# non_inverting_amplifier_2.net
KiCad netlist of a schematic drawn in EAGLE
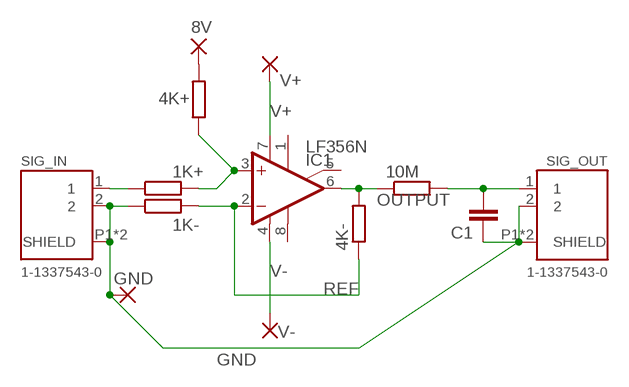
[diagram p0: schematic, sheet 1]

(export (version "E")
  (design (tool "Eeschema 10.0.6"))
  (components
    (comp (ref "1K+")
      (value "R-EU_0207/12")
      (footprint "eagle-import:0207_12")
      (libsource (lib "eagle-import") (part "R-EU_0207/12"))
    )
    (comp (ref "1K-")
      (value "R-EU_0207/12")
      (footprint "eagle-import:0207_12")
      (libsource (lib "eagle-import") (part "R-EU_0207/12"))
    )
    (comp (ref "4K+")
      (value "R-EU_0207/12")
      (footprint "eagle-import:0207_12")
      (libsource (lib "eagle-import") (part "R-EU_0207/12"))
    )
    (comp (ref "4K-")
      (value "R-EU_0207/12")
      (footprint "eagle-import:0207_12")
      (libsource (lib "eagle-import") (part "R-EU_0207/12"))
    )
    (comp (ref "8V")
      (value "2,54/1,1")
      (footprint "eagle-import:2,54_1,1")
      (libsource (lib "eagle-import") (part "2,54/1,1"))
    )
    (comp (ref "10M")
      (value "R-EU_0207/12")
      (footprint "eagle-import:0207_12")
      (libsource (lib "eagle-import") (part "R-EU_0207/12"))
    )
    (comp (ref "C1")
      (value "C2,5-3")
      (footprint "eagle-import:C2.5-3")
      (libsource (lib "eagle-import") (part "C2,5-3"))
    )
    (comp (ref "GND")
      (value "2,54/1,1")
      (footprint "eagle-import:2,54_1,1")
      (libsource (lib "eagle-import") (part "2,54/1,1"))
    )
    (comp (ref "IC1")
      (value "LF356N")
      (footprint "eagle-import:DIL08")
      (libsource (lib "eagle-import") (part "LF356N"))
    )
    (comp (ref "SIG_IN")
      (value "1-1337543-0")
      (footprint "eagle-import:CONN_1-1337543-0")
      (fields (field (name "DIGI-KEY_PART_NUMBER") "A97553-ND") (field (name "MF") "TE Connectivity"))
      (libsource (lib "eagle-import") (part "1-1337543-0"))
    )
    (comp (ref "SIG_OUT")
      (value "1-1337543-0")
      (footprint "eagle-import:CONN_1-1337543-0")
      (fields (field (name "DIGI-KEY_PART_NUMBER") "A97553-ND") (field (name "MF") "TE Connectivity"))
      (libsource (lib "eagle-import") (part "1-1337543-0"))
    )
    (comp (ref "V+")
      (value "2,54/1,1")
      (footprint "eagle-import:2,54_1,1")
      (libsource (lib "eagle-import") (part "2,54/1,1"))
    )
    (comp (ref "V-")
      (value "2,54/1,1")
      (footprint "eagle-import:2,54_1,1")
      (libsource (lib "eagle-import") (part "2,54/1,1"))
    )
  )
  (nets
    (net (code "1") (name "/GND") (class "Default")
      (node (ref "1K-") (pin "1") (pinfunction "1_1") (pintype "passive"))
      (node (ref "C1") (pin "1") (pinfunction "1_1") (pintype "passive"))
      (node (ref "GND") (pin "1") (pinfunction "P_1") (pintype "passive"))
      (node (ref "SIG_IN") (pin "2") (pinfunction "2_2") (pintype "passive"))
      (node (ref "SIG_IN") (pin "P1") (pinfunction "SHIELD_P1") (pintype "passive"))
      (node (ref "SIG_IN") (pin "P2") (pinfunction "SHIELD_P2") (pintype "passive"))
      (node (ref "SIG_OUT") (pin "2") (pinfunction "2_2") (pintype "passive"))
      (node (ref "SIG_OUT") (pin "P1") (pinfunction "SHIELD_P1") (pintype "passive"))
      (node (ref "SIG_OUT") (pin "P2") (pinfunction "SHIELD_P2") (pintype "passive"))
    )
    (net (code "2") (name "/OUTPUT") (class "Default")
      (node (ref "10M") (pin "1") (pinfunction "1_1") (pintype "passive"))
      (node (ref "4K-") (pin "2") (pinfunction "2_2") (pintype "passive"))
      (node (ref "IC1") (pin "6") (pinfunction "OUT_6") (pintype "output"))
    )
    (net (code "3") (name "/REF") (class "Default")
      (node (ref "1K-") (pin "2") (pinfunction "2_2") (pintype "passive"))
      (node (ref "4K-") (pin "1") (pinfunction "1_1") (pintype "passive"))
      (node (ref "IC1") (pin "2") (pinfunction "-IN_2") (pintype "input"))
    )
    (net (code "4") (name "/V+") (class "Default")
      (node (ref "IC1") (pin "7") (pinfunction "V+_7") (pintype "power_in"))
      (node (ref "V+") (pin "1") (pinfunction "P_1") (pintype "passive"))
    )
    (net (code "5") (name "/V-") (class "Default")
      (node (ref "IC1") (pin "4") (pinfunction "V-_4") (pintype "power_in"))
      (node (ref "V-") (pin "1") (pinfunction "P_1") (pintype "passive"))
    )
    (net (code "6") (name "Net-(1K+-Pad1)") (class "Default")
      (node (ref "1K+") (pin "1") (pinfunction "1_1") (pintype "passive"))
      (node (ref "SIG_IN") (pin "1") (pinfunction "1_1") (pintype "passive"))
    )
    (net (code "7") (name "Net-(8V-P)") (class "Default")
      (node (ref "4K+") (pin "2") (pinfunction "2_2") (pintype "passive"))
      (node (ref "8V") (pin "1") (pinfunction "P_1") (pintype "passive"))
    )
    (net (code "8") (name "Net-(10M-Pad2)") (class "Default")
      (node (ref "10M") (pin "2") (pinfunction "2_2") (pintype "passive"))
      (node (ref "C1") (pin "2") (pinfunction "2_2") (pintype "passive"))
      (node (ref "SIG_OUT") (pin "1") (pinfunction "1_1") (pintype "passive"))
    )
    (net (code "9") (name "Net-(IC1-+IN)") (class "Default")
      (node (ref "1K+") (pin "2") (pinfunction "2_2") (pintype "passive"))
      (node (ref "4K+") (pin "1") (pinfunction "1_1") (pintype "passive"))
      (node (ref "IC1") (pin "3") (pinfunction "+IN_3") (pintype "input"))
    )
    (net (code "10") (name "unconnected-(IC1-ON1-Pad1)") (class "Default")
      (node (ref "IC1") (pin "1") (pinfunction "ON1_1") (pintype "passive"))
    )
    (net (code "11") (name "unconnected-(IC1-ON2-Pad5)") (class "Default")
      (node (ref "IC1") (pin "5") (pinfunction "ON2_5") (pintype "passive"))
    )
    (net (code "12") (name "unconnected-(IC1-OPT-Pad8)") (class "Default")
      (node (ref "IC1") (pin "8") (pinfunction "OPT_8") (pintype "passive"))
    )
  )
)
